# ControllerBase.net
KiCad netlist of a schematic drawn in EAGLE
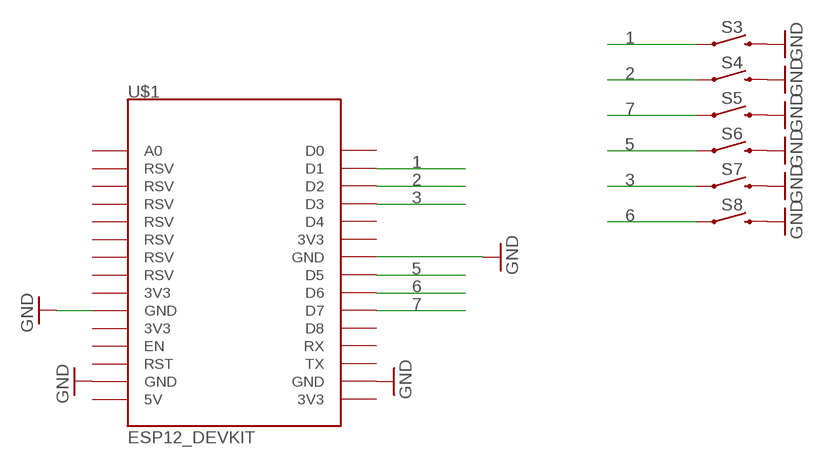
[diagram p0: schematic, sheet 1]

(export (version "E")
  (design (tool "Eeschema 10.0.6"))
  (components
    (comp (ref "S3")
      (value "MOMENTARY-SWITCH-SPST-PTH-6.0MM")
      (footprint "eagle-import:TACTILE_SWITCH_PTH_6.0MM")
      (libsource (lib "eagle-import") (part "MOMENTARY-SWITCH-SPST-PTH-6.0MM"))
    )
    (comp (ref "S4")
      (value "MOMENTARY-SWITCH-SPST-PTH-6.0MM")
      (footprint "eagle-import:TACTILE_SWITCH_PTH_6.0MM")
      (libsource (lib "eagle-import") (part "MOMENTARY-SWITCH-SPST-PTH-6.0MM"))
    )
    (comp (ref "S5")
      (value "MOMENTARY-SWITCH-SPST-PTH-6.0MM")
      (footprint "eagle-import:TACTILE_SWITCH_PTH_6.0MM")
      (libsource (lib "eagle-import") (part "MOMENTARY-SWITCH-SPST-PTH-6.0MM"))
    )
    (comp (ref "S6")
      (value "MOMENTARY-SWITCH-SPST-PTH-6.0MM")
      (footprint "eagle-import:TACTILE_SWITCH_PTH_6.0MM")
      (libsource (lib "eagle-import") (part "MOMENTARY-SWITCH-SPST-PTH-6.0MM"))
    )
    (comp (ref "S7")
      (value "MOMENTARY-SWITCH-SPST-PTH-6.0MM")
      (footprint "eagle-import:TACTILE_SWITCH_PTH_6.0MM")
      (libsource (lib "eagle-import") (part "MOMENTARY-SWITCH-SPST-PTH-6.0MM"))
    )
    (comp (ref "S8")
      (value "MOMENTARY-SWITCH-SPST-PTH-6.0MM")
      (footprint "eagle-import:TACTILE_SWITCH_PTH_6.0MM")
      (libsource (lib "eagle-import") (part "MOMENTARY-SWITCH-SPST-PTH-6.0MM"))
    )
    (comp (ref "U$1")
      (value "ESP12_DEVKIT")
      (footprint "eagle-import:ESP12_DEVKIT")
      (libsource (lib "eagle-import") (part "ESP12_DEVKIT"))
    )
  )
  (nets
    (net (code "1") (name "/1") (class "Default")
      (node (ref "S3") (pin "1") (pinfunction "1_1") (pintype "passive"))
      (node (ref "U$1") (pin "D1") (pinfunction "D1_D1") (pintype "bidirectional"))
    )
    (net (code "2") (name "/2") (class "Default")
      (node (ref "S4") (pin "1") (pinfunction "1_1") (pintype "passive"))
      (node (ref "U$1") (pin "D2") (pinfunction "D2_D2") (pintype "bidirectional"))
    )
    (net (code "3") (name "/3") (class "Default")
      (node (ref "S7") (pin "1") (pinfunction "1_1") (pintype "passive"))
      (node (ref "U$1") (pin "D3") (pinfunction "D3_D3") (pintype "bidirectional"))
    )
    (net (code "4") (name "/5") (class "Default")
      (node (ref "S6") (pin "1") (pinfunction "1_1") (pintype "passive"))
      (node (ref "U$1") (pin "D5") (pinfunction "D5_D5") (pintype "bidirectional"))
    )
    (net (code "5") (name "/6") (class "Default")
      (node (ref "S8") (pin "1") (pinfunction "1_1") (pintype "passive"))
      (node (ref "U$1") (pin "D6") (pinfunction "D6_D6") (pintype "bidirectional"))
    )
    (net (code "6") (name "/7") (class "Default")
      (node (ref "S5") (pin "1") (pinfunction "1_1") (pintype "passive"))
      (node (ref "U$1") (pin "D7") (pinfunction "D7_D7") (pintype "bidirectional"))
    )
    (net (code "7") (name "GND") (class "Default")
      (node (ref "S3") (pin "3") (pinfunction "2_3") (pintype "passive"))
      (node (ref "S4") (pin "3") (pinfunction "2_3") (pintype "passive"))
      (node (ref "S5") (pin "3") (pinfunction "2_3") (pintype "passive"))
      (node (ref "S6") (pin "3") (pinfunction "2_3") (pintype "passive"))
      (node (ref "S7") (pin "3") (pinfunction "2_3") (pintype "passive"))
      (node (ref "S8") (pin "3") (pinfunction "2_3") (pintype "passive"))
      (node (ref "U$1") (pin "GND@0") (pinfunction "GND_GND@0") (pintype "bidirectional"))
      (node (ref "U$1") (pin "GND@1") (pinfunction "GND_GND@1") (pintype "bidirectional"))
      (node (ref "U$1") (pin "GND@2") (pinfunction "GND_GND@2") (pintype "bidirectional"))
      (node (ref "U$1") (pin "GND@3") (pinfunction "GND_GND@3") (pintype "bidirectional"))
    )
    (net (code "8") (name "unconnected-(U$1-3V3-Pad3V3@0)") (class "Default")
      (node (ref "U$1") (pin "3V3@0") (pinfunction "3V3_3V3@0") (pintype "bidirectional"))
    )
    (net (code "9") (name "unconnected-(U$1-3V3-Pad3V3@1)") (class "Default")
      (node (ref "U$1") (pin "3V3@1") (pinfunction "3V3_3V3@1") (pintype "bidirectional"))
    )
    (net (code "10") (name "unconnected-(U$1-3V3-Pad3V3@2)") (class "Default")
      (node (ref "U$1") (pin "3V3@2") (pinfunction "3V3_3V3@2") (pintype "bidirectional"))
    )
    (net (code "11") (name "unconnected-(U$1-3V3-Pad3V3@3)") (class "Default")
      (node (ref "U$1") (pin "3V3@3") (pinfunction "3V3_3V3@3") (pintype "bidirectional"))
    )
    (net (code "12") (name "unconnected-(U$1-Pad5V)") (class "Default")
      (node (ref "U$1") (pin "5V") (pinfunction "5V_5V") (pintype "bidirectional"))
    )
    (net (code "13") (name "unconnected-(U$1-PadA0)") (class "Default")
      (node (ref "U$1") (pin "A0") (pinfunction "A0_A0") (pintype "bidirectional"))
    )
    (net (code "14") (name "unconnected-(U$1-PadD0)") (class "Default")
      (node (ref "U$1") (pin "D0") (pinfunction "D0_D0") (pintype "bidirectional"))
    )
    (net (code "15") (name "unconnected-(U$1-PadD4)") (class "Default")
      (node (ref "U$1") (pin "D4") (pinfunction "D4_D4") (pintype "bidirectional"))
    )
    (net (code "16") (name "unconnected-(U$1-PadD8)") (class "Default")
      (node (ref "U$1") (pin "D8") (pinfunction "D8_D8") (pintype "bidirectional"))
    )
    (net (code "17") (name "unconnected-(U$1-PadEN)") (class "Default")
      (node (ref "U$1") (pin "EN") (pinfunction "EN_EN") (pintype "bidirectional"))
    )
    (net (code "18") (name "unconnected-(U$1-PadRST)") (class "Default")
      (node (ref "U$1") (pin "RST") (pinfunction "RST_RST") (pintype "bidirectional"))
    )
    (net (code "19") (name "unconnected-(U$1-PadRX)") (class "Default")
      (node (ref "U$1") (pin "RX") (pinfunction "RX_RX") (pintype "bidirectional"))
    )
    (net (code "20") (name "unconnected-(U$1-PadTX)") (class "Default")
      (node (ref "U$1") (pin "TX") (pinfunction "TX_TX") (pintype "bidirectional"))
    )
    (net (code "21") (name "unconnected-(U$1-RSV-PadGND@4)") (class "Default")
      (node (ref "U$1") (pin "GND@4") (pinfunction "RSV_GND@4") (pintype "bidirectional"))
    )
    (net (code "22") (name "unconnected-(U$1-RSV-PadRSV@0)") (class "Default")
      (node (ref "U$1") (pin "RSV@0") (pinfunction "RSV_RSV@0") (pintype "bidirectional"))
    )
    (net (code "23") (name "unconnected-(U$1-RSV-PadRSV@1)") (class "Default")
      (node (ref "U$1") (pin "RSV@1") (pinfunction "RSV_RSV@1") (pintype "bidirectional"))
    )
    (net (code "24") (name "unconnected-(U$1-RSV-PadRSV@2)") (class "Default")
      (node (ref "U$1") (pin "RSV@2") (pinfunction "RSV_RSV@2") (pintype "bidirectional"))
    )
    (net (code "25") (name "unconnected-(U$1-RSV-PadRSV@3)") (class "Default")
      (node (ref "U$1") (pin "RSV@3") (pinfunction "RSV_RSV@3") (pintype "bidirectional"))
    )
    (net (code "26") (name "unconnected-(U$1-RSV-PadRSV@4)") (class "Default")
      (node (ref "U$1") (pin "RSV@4") (pinfunction "RSV_RSV@4") (pintype "bidirectional"))
    )
    (net (code "27") (name "unconnected-(U$1-RSV-PadRSV@5)") (class "Default")
      (node (ref "U$1") (pin "RSV@5") (pinfunction "RSV_RSV@5") (pintype "bidirectional"))
    )
  )
)
